# luoye-microphone-board-2026-08-30.net
KiCad netlist of a schematic drawn in EasyEDA Pro
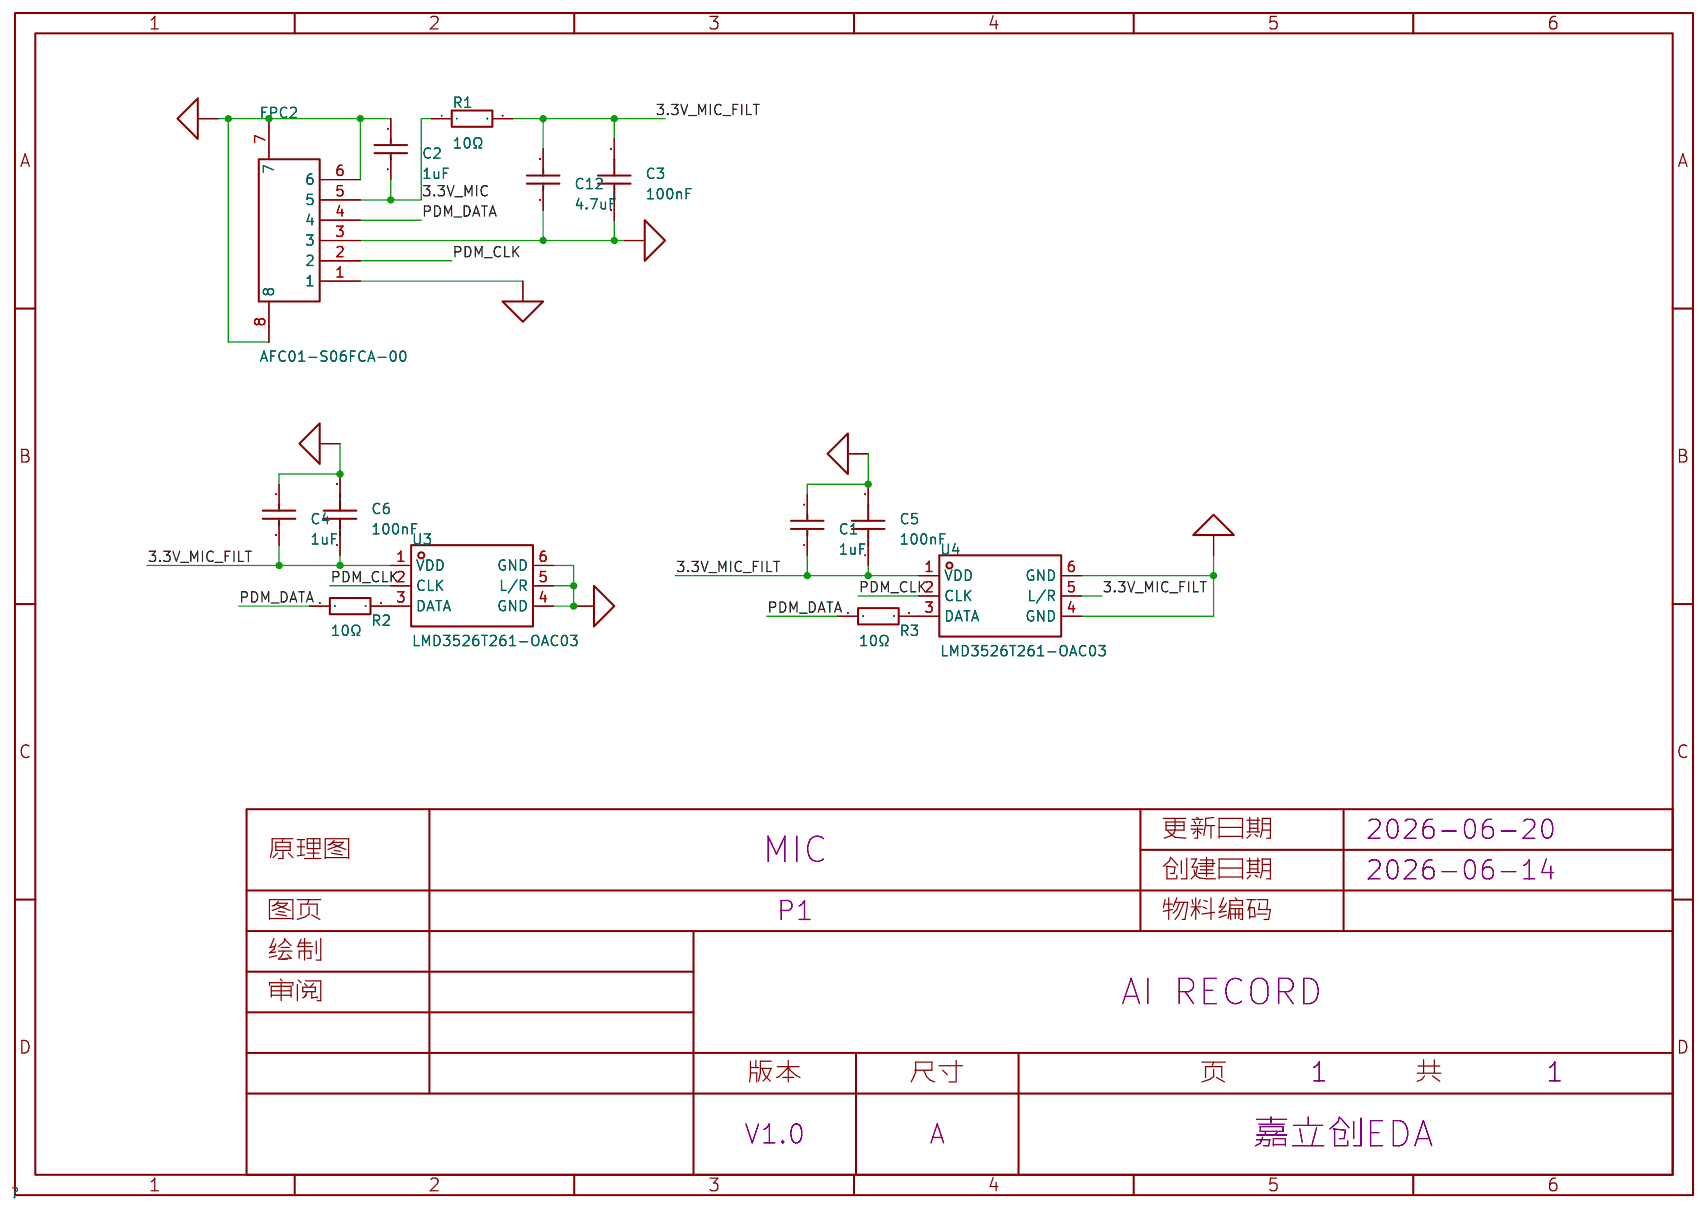
[diagram p0: schematic sheet]

(export (version "E")
  (design (tool "Eeschema 10.0.6"))
  (components
    (comp (ref "C1")
      (value "1uF")
      (footprint "easyedapro:C0402")
      (description "容值:1uF;精度:±10%;额定电压:16V;温度系数:X5R;")
      (fields
        (field (name "Manufacturer Part") "CL05A105KO5NNNC")
        (field (name "Manufacturer") "SAMSUNG(三星)")
      )
      (libsource (lib "easyedapro") (part "CL05A105KO5NNNC"))
    )
    (comp (ref "C2")
      (value "1uF")
      (footprint "easyedapro:C0402")
      (description "容值:1uF;精度:±10%;额定电压:16V;温度系数:X5R;")
      (fields
        (field (name "Manufacturer Part") "CL05A105KO5NNNC")
        (field (name "Manufacturer") "SAMSUNG(三星)")
      )
      (libsource (lib "easyedapro") (part "CL05A105KO5NNNC"))
    )
    (comp (ref "C3")
      (value "100nF")
      (footprint "easyedapro:C0402")
      (description "容值:100nF;精度:±10%;额定电压:16V;温度系数:X7R;")
      (fields
        (field (name "Manufacturer Part") "CL05B104KO5NNNC")
        (field (name "Manufacturer") "SAMSUNG(三星)")
      )
      (libsource (lib "easyedapro") (part "CL05B104KO5NNNC"))
    )
    (comp (ref "C4")
      (value "1uF")
      (footprint "easyedapro:C0402")
      (description "容值:1uF;精度:±10%;额定电压:16V;温度系数:X5R;")
      (fields
        (field (name "Manufacturer Part") "CL05A105KO5NNNC")
        (field (name "Manufacturer") "SAMSUNG(三星)")
      )
      (libsource (lib "easyedapro") (part "CL05A105KO5NNNC"))
    )
    (comp (ref "C5")
      (value "100nF")
      (footprint "easyedapro:C0402")
      (description "容值:100nF;精度:±10%;额定电压:16V;温度系数:X7R;")
      (fields
        (field (name "Manufacturer Part") "CL05B104KO5NNNC")
        (field (name "Manufacturer") "SAMSUNG(三星)")
      )
      (libsource (lib "easyedapro") (part "CL05B104KO5NNNC"))
    )
    (comp (ref "C6")
      (value "100nF")
      (footprint "easyedapro:C0402")
      (description "容值:100nF;精度:±10%;额定电压:16V;温度系数:X7R;")
      (fields
        (field (name "Manufacturer Part") "CL05B104KO5NNNC")
        (field (name "Manufacturer") "SAMSUNG(三星)")
      )
      (libsource (lib "easyedapro") (part "CL05B104KO5NNNC"))
    )
    (comp (ref "C12")
      (value "4.7uF")
      (footprint "easyedapro:C0805")
      (description "容值:4.7uF;精度:±10%;额定电压:25V;温度系数:X5R;")
      (fields
        (field (name "Manufacturer Part") "CL21A475KAQNNNE")
        (field (name "Manufacturer") "SAMSUNG(三星)")
      )
      (libsource (lib "easyedapro") (part "CL21A475KAQNNNE"))
    )
    (comp (ref "FPC2")
      (value "AFC01-S06FCA-00")
      (footprint "easyedapro:FPC-SMD_P0.50-6P_AFC01-S06FCA-00")
      (fields (field (name "Manufacturer") "JS(钜硕电子)"))
      (libsource (lib "easyedapro") (part "AFC01-S06FCA-00"))
    )
    (comp (ref "R1")
      (value "10Ω")
      (footprint "easyedapro:R0805")
      (fields (field (name "Manufacturer Part") "RC0805FR-0710RL") (field (name "Manufacturer") "YAGEO(国巨)"))
      (libsource (lib "easyedapro") (part "RC0805FR-0710RL"))
    )
    (comp (ref "R2")
      (value "10Ω")
      (footprint "easyedapro:R0805")
      (description "电阻类型:厚膜电阻;阻值:10Ω;精度:±1%;功率:125mW;工作电压:150V;温度系数:±200ppm/℃;")
      (fields (field (name "Manufacturer Part") "RC0805FR-0710RL") (field (name "Manufacturer") "YAGEO(国巨)"))
      (libsource (lib "easyedapro") (part "RC0805FR-0710RL"))
    )
    (comp (ref "R3")
      (value "10Ω")
      (footprint "easyedapro:R0805")
      (description "电阻类型:厚膜电阻;阻值:10Ω;精度:±1%;功率:125mW;工作电压:150V;温度系数:±200ppm/℃;")
      (fields (field (name "Manufacturer Part") "RC0805FR-0710RL") (field (name "Manufacturer") "YAGEO(国巨)"))
      (libsource (lib "easyedapro") (part "RC0805FR-0710RL"))
    )
    (comp (ref "U3")
      (value "LMD3526T261-OAC03")
      (footprint "easyedapro:MIC-SMD_6P-L3.5-W2.7-P0.884-TR")
      (description "方向:全指向;灵敏度:-26dB;")
      (fields (field (name "Manufacturer") "LinkMems(聆麦声学)"))
      (libsource (lib "easyedapro") (part "LMD3526T261-OAC03"))
    )
    (comp (ref "U4")
      (value "LMD3526T261-OAC03")
      (footprint "easyedapro:MIC-SMD_6P-L3.5-W2.7-P0.884-TR")
      (description "方向:全指向;灵敏度:-26dB;")
      (fields (field (name "Manufacturer") "LinkMems(聆麦声学)"))
      (libsource (lib "easyedapro") (part "LMD3526T261-OAC03"))
    )
  )
  (nets
    (net (code "1") (name "/3.3V_MIC") (class "Default")
      (node (ref "C2") (pin "2") (pinfunction "2_2") (pintype "input"))
      (node (ref "FPC2") (pin "5") (pinfunction "5_5") (pintype "unspecified"))
      (node (ref "R1") (pin "1") (pinfunction "1_1") (pintype "input"))
    )
    (net (code "2") (name "/3.3V_MIC_FILT") (class "Default")
      (node (ref "C1") (pin "1") (pinfunction "1_1") (pintype "input"))
      (node (ref "C12") (pin "2") (pinfunction "2_2") (pintype "input"))
      (node (ref "C3") (pin "2") (pinfunction "2_2") (pintype "unspecified"))
      (node (ref "C4") (pin "1") (pinfunction "1_1") (pintype "input"))
      (node (ref "C5") (pin "1") (pinfunction "1_1") (pintype "unspecified"))
      (node (ref "C6") (pin "1") (pinfunction "1_1") (pintype "unspecified"))
      (node (ref "R1") (pin "2") (pinfunction "2_2") (pintype "input"))
      (node (ref "U3") (pin "1") (pinfunction "VDD_1") (pintype "unspecified"))
      (node (ref "U4") (pin "1") (pinfunction "VDD_1") (pintype "unspecified"))
      (node (ref "U4") (pin "5") (pinfunction "L/R_5") (pintype "unspecified"))
    )
    (net (code "3") (name "/PDM_CLK") (class "Default")
      (node (ref "FPC2") (pin "2") (pinfunction "2_2") (pintype "unspecified"))
      (node (ref "U3") (pin "2") (pinfunction "CLK_2") (pintype "unspecified"))
      (node (ref "U4") (pin "2") (pinfunction "CLK_2") (pintype "unspecified"))
    )
    (net (code "4") (name "/PDM_DATA") (class "Default")
      (node (ref "FPC2") (pin "4") (pinfunction "4_4") (pintype "unspecified"))
      (node (ref "R2") (pin "1") (pinfunction "1_1") (pintype "input"))
      (node (ref "R3") (pin "1") (pinfunction "1_1") (pintype "input"))
    )
    (net (code "5") (name "AGND") (class "Default")
      (node (ref "C1") (pin "2") (pinfunction "2_2") (pintype "input"))
      (node (ref "C12") (pin "1") (pinfunction "1_1") (pintype "input"))
      (node (ref "C2") (pin "1") (pinfunction "1_1") (pintype "input"))
      (node (ref "C3") (pin "1") (pinfunction "1_1") (pintype "unspecified"))
      (node (ref "C4") (pin "2") (pinfunction "2_2") (pintype "input"))
      (node (ref "C5") (pin "2") (pinfunction "2_2") (pintype "unspecified"))
      (node (ref "C6") (pin "2") (pinfunction "2_2") (pintype "unspecified"))
      (node (ref "FPC2") (pin "1") (pinfunction "1_1") (pintype "unspecified"))
      (node (ref "FPC2") (pin "3") (pinfunction "3_3") (pintype "unspecified"))
      (node (ref "FPC2") (pin "6") (pinfunction "6_6") (pintype "unspecified"))
      (node (ref "FPC2") (pin "7") (pinfunction "7_7") (pintype "unspecified"))
      (node (ref "FPC2") (pin "8") (pinfunction "8_8") (pintype "unspecified"))
      (node (ref "U3") (pin "4") (pinfunction "GND_4") (pintype "unspecified"))
      (node (ref "U3") (pin "5") (pinfunction "L/R_5") (pintype "unspecified"))
      (node (ref "U3") (pin "6") (pinfunction "GND_6") (pintype "unspecified"))
      (node (ref "U4") (pin "4") (pinfunction "GND_4") (pintype "unspecified"))
      (node (ref "U4") (pin "6") (pinfunction "GND_6") (pintype "unspecified"))
    )
    (net (code "6") (name "Net-(U3-DATA)") (class "Default")
      (node (ref "R2") (pin "2") (pinfunction "2_2") (pintype "input"))
      (node (ref "U3") (pin "3") (pinfunction "DATA_3") (pintype "unspecified"))
    )
    (net (code "7") (name "Net-(U4-DATA)") (class "Default")
      (node (ref "R3") (pin "2") (pinfunction "2_2") (pintype "input"))
      (node (ref "U4") (pin "3") (pinfunction "DATA_3") (pintype "unspecified"))
    )
  )
)
